# STM32G474R.net
KiCad netlist of a schematic drawn in Altium Designer
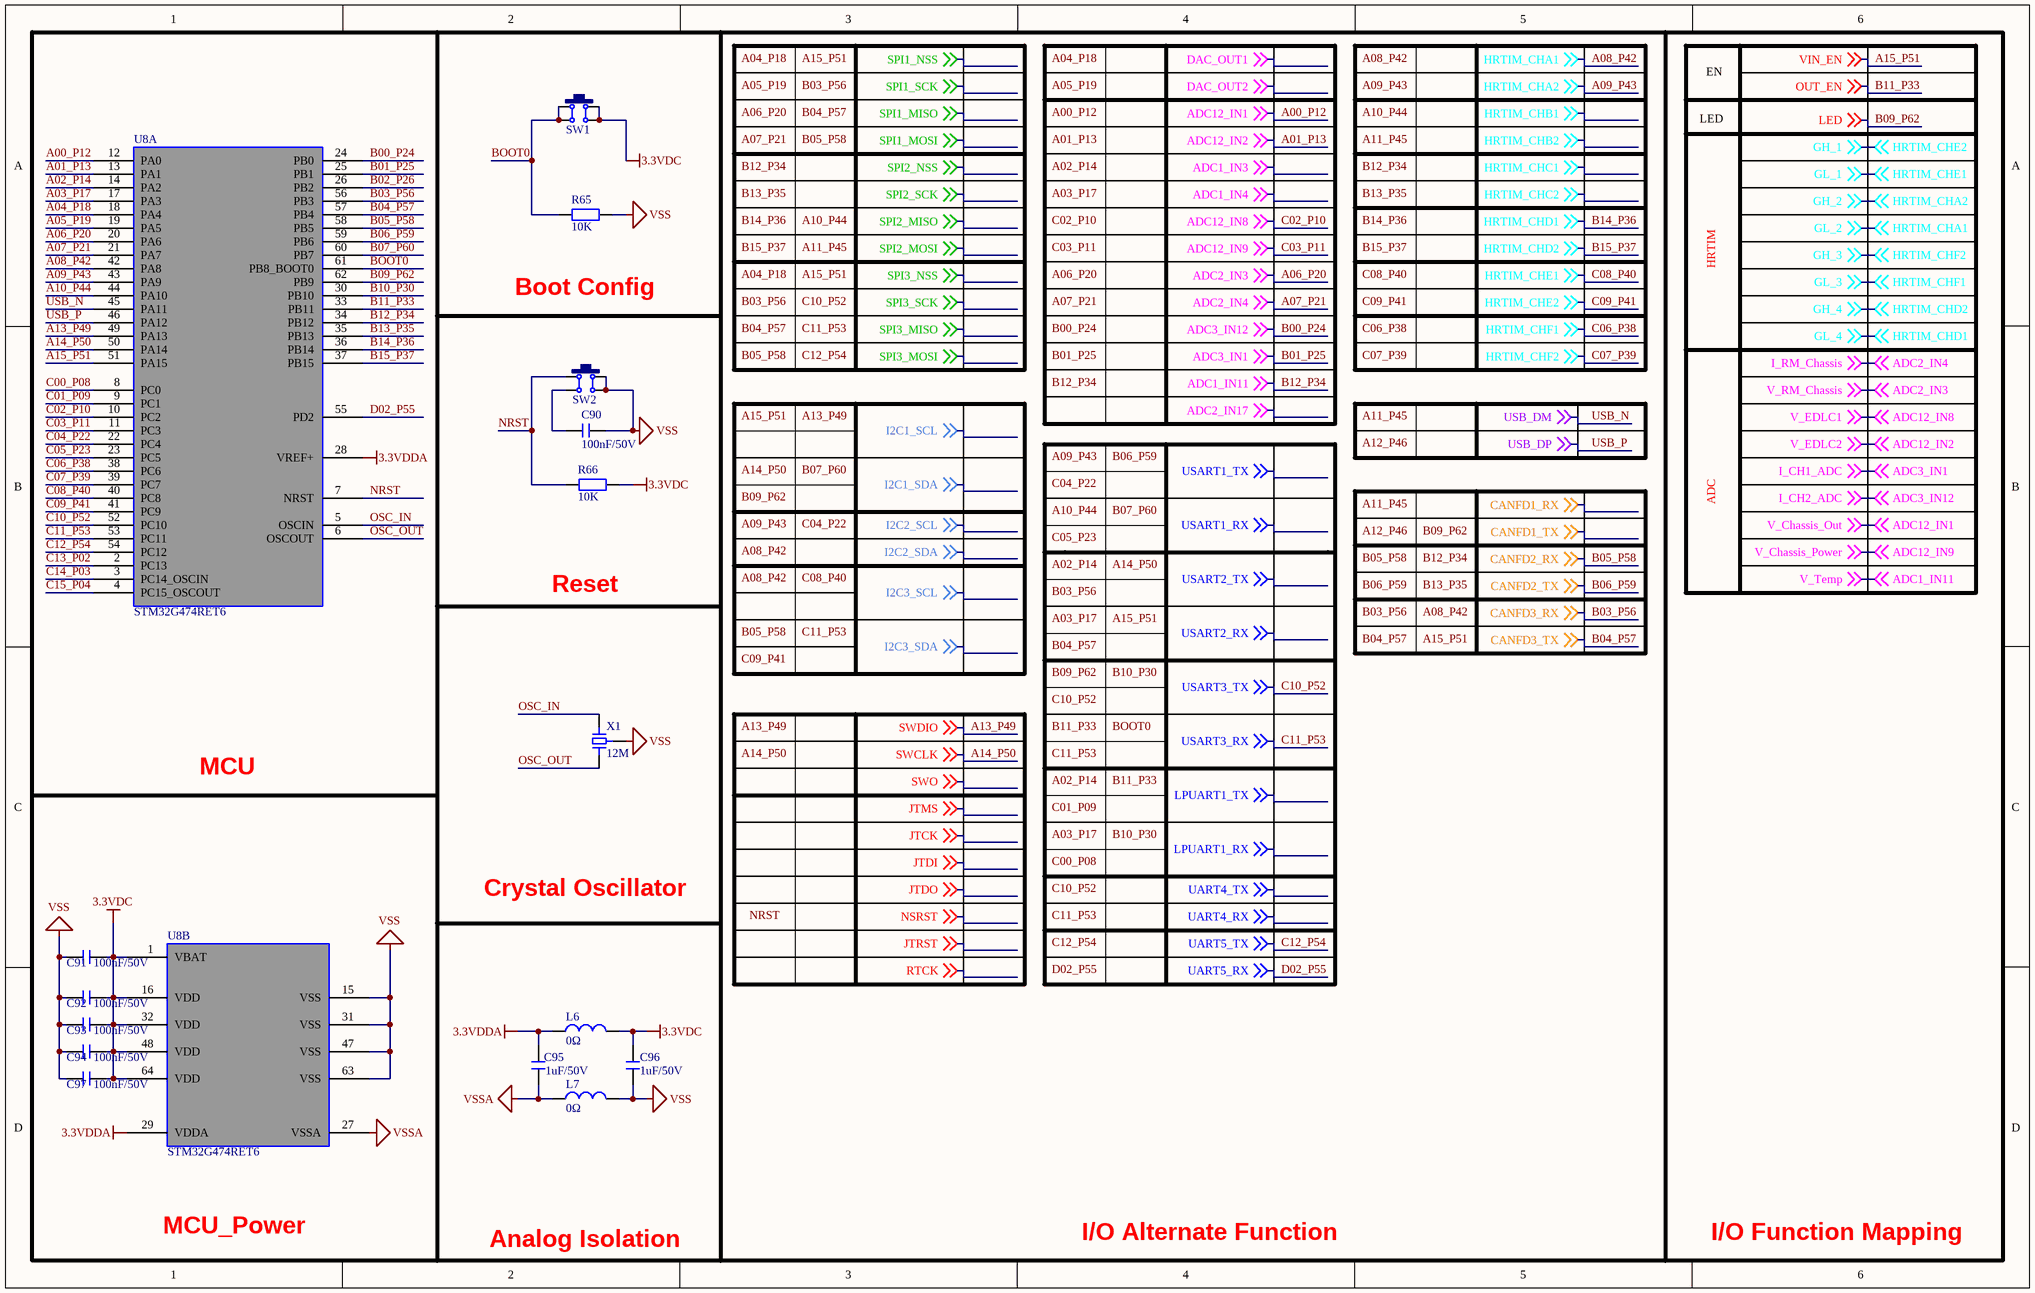
[diagram p0: STM32G474R.SchDoc]

(export (version "E")
  (design (tool "Eeschema 10.0.6"))
  (components
    (comp (ref "C90")
      (value "100nF/50V")
      (footprint "C 0603_L")
      (description "无极性贴片电容")
      (fields (field (name "版权归属") "源创客"))
      (libsource (lib "3.2-电容") (part "C"))
    )
    (comp (ref "C91")
      (value "100nF/50V")
      (footprint "C 0603_L")
      (description "无极性贴片电容")
      (fields (field (name "版权归属") "源创客"))
      (libsource (lib "3.2-电容") (part "C"))
    )
    (comp (ref "C92")
      (value "100nF/50V")
      (footprint "C 0603_L")
      (description "无极性贴片电容")
      (fields (field (name "版权归属") "源创客"))
      (libsource (lib "3.2-电容") (part "C"))
    )
    (comp (ref "C93")
      (value "100nF/50V")
      (footprint "C 0603_L")
      (description "无极性贴片电容")
      (fields (field (name "版权归属") "源创客"))
      (libsource (lib "3.2-电容") (part "C"))
    )
    (comp (ref "C94")
      (value "100nF/50V")
      (footprint "C 0603_L")
      (description "无极性贴片电容")
      (fields (field (name "版权归属") "源创客"))
      (libsource (lib "3.2-电容") (part "C"))
    )
    (comp (ref "C95")
      (value "1uF/50V")
      (footprint "C 0603_L")
      (description "无极性贴片电容")
      (fields (field (name "版权归属") "源创客"))
      (libsource (lib "3.2-电容") (part "C"))
    )
    (comp (ref "C96")
      (value "1uF/50V")
      (footprint "C 0603_L")
      (description "无极性贴片电容")
      (fields (field (name "版权归属") "源创客"))
      (libsource (lib "3.2-电容") (part "C"))
    )
    (comp (ref "C97")
      (value "100nF/50V")
      (footprint "C 0603_L")
      (description "无极性贴片电容")
      (fields (field (name "版权归属") "源创客"))
      (libsource (lib "3.2-电容") (part "C"))
    )
    (comp (ref "L6")
      (value "0Ω")
      (footprint "L 0603")
      (description "小功率贴片电感")
      (fields (field (name "版权归属") "源创客"))
      (libsource (lib "3.3-电感") (part "L"))
    )
    (comp (ref "L7")
      (value "0Ω")
      (footprint "L 0603")
      (description "小功率贴片电感")
      (fields (field (name "版权归属") "源创客"))
      (libsource (lib "3.3-电感") (part "L"))
    )
    (comp (ref "R65")
      (value "10K")
      (footprint "R 0603_L")
      (description "贴片电阻")
      (fields (field (name "版权归属") "源创客"))
      (libsource (lib "3.1-电阻") (part "R"))
    )
    (comp (ref "R66")
      (value "10K")
      (footprint "R 0603_L")
      (description "贴片电阻")
      (fields (field (name "版权归属") "源创客"))
      (libsource (lib "3.1-电阻") (part "R"))
    )
    (comp (ref "SW1")
      (value "3.2x4.2x2.5")
      (footprint "TSW SMD-3.2*4.2*2.5")
      (description "3.2x4.2轻触开关")
      (fields (field (name "版权归属") "源创客"))
      (libsource (lib "6.1-按键") (part "TSW SMD-3x4_D"))
    )
    (comp (ref "SW2")
      (value "3.2x4.2x2.5")
      (footprint "TSW SMD-3.2*4.2*2.5")
      (description "3.2x4.2轻触开关")
      (fields (field (name "版权归属") "源创客"))
      (libsource (lib "6.1-按键") (part "TSW SMD-3x4_D"))
    )
    (comp (ref "U8")
      (value "STM32G474RET6")
      (footprint "LQFP64-10*10")
      (libsource (lib "2.5-STM32G4单片机") (part "STM32G474RET6"))
    )
    (comp (ref "X1")
      (value "12M")
      (footprint "OSC 3213-3P")
      (description "3脚内置电容无源晶振")
      (libsource (lib "8.1-晶振") (part "XTAL-3P"))
    )
  )
  (nets
    (net (code "2") (name "/A02_P14") (class "Default")
      (node (ref "U8") (pin "14") (pinfunction "PA2_14") (pintype "passive"))
    )
    (net (code "3") (name "/A03_P17") (class "Default")
      (node (ref "U8") (pin "17") (pinfunction "PA3_17") (pintype "passive"))
    )
    (net (code "4") (name "/A04_P18") (class "Default")
      (node (ref "U8") (pin "18") (pinfunction "PA4_18") (pintype "passive"))
    )
    (net (code "5") (name "/A05_P19") (class "Default")
      (node (ref "U8") (pin "19") (pinfunction "PA5_19") (pintype "passive"))
    )
    (net (code "6") (name "/A10_P44") (class "Default")
      (node (ref "U8") (pin "44") (pinfunction "PA10_44") (pintype "passive"))
    )
    (net (code "9") (name "/B02_P26") (class "Default")
      (node (ref "U8") (pin "26") (pinfunction "PB2_26") (pintype "passive"))
    )
    (net (code "10") (name "/B07_P60") (class "Default")
      (node (ref "U8") (pin "60") (pinfunction "PB7_60") (pintype "passive"))
    )
    (net (code "11") (name "/B10_P30") (class "Default")
      (node (ref "U8") (pin "30") (pinfunction "PB10_30") (pintype "passive"))
    )
    (net (code "12") (name "/B13_P35") (class "Default")
      (node (ref "U8") (pin "35") (pinfunction "PB13_35") (pintype "passive"))
    )
    (net (code "13") (name "/BOOT0") (class "Default")
      (node (ref "R65") (pin "2") (pinfunction "2_2") (pintype "passive"))
      (node (ref "SW1") (pin "2") (pinfunction "2_2") (pintype "passive"))
      (node (ref "SW1") (pin "3") (pinfunction "3_3") (pintype "passive"))
      (node (ref "U8") (pin "61") (pinfunction "PB8_BOOT0_61") (pintype "passive"))
    )
    (net (code "14") (name "/C00_P08") (class "Default")
      (node (ref "U8") (pin "8") (pinfunction "PC0_8") (pintype "passive"))
    )
    (net (code "15") (name "/C01_P09") (class "Default")
      (node (ref "U8") (pin "9") (pinfunction "PC1_9") (pintype "passive"))
    )
    (net (code "16") (name "/C04_P22") (class "Default")
      (node (ref "U8") (pin "22") (pinfunction "PC4_22") (pintype "passive"))
    )
    (net (code "17") (name "/C05_P23") (class "Default")
      (node (ref "U8") (pin "23") (pinfunction "PC5_23") (pintype "passive"))
    )
    (net (code "18") (name "/C13_P02") (class "Default")
      (node (ref "U8") (pin "2") (pinfunction "PC13_2") (pintype "passive"))
    )
    (net (code "19") (name "/C14_P03") (class "Default")
      (node (ref "U8") (pin "3") (pinfunction "PC14_OSCIN_3") (pintype "passive"))
    )
    (net (code "20") (name "/C15_P04") (class "Default")
      (node (ref "U8") (pin "4") (pinfunction "PC15_OSCOUT_4") (pintype "passive"))
    )
    (net (code "21") (name "/NRST") (class "Default")
      (node (ref "R66") (pin "2") (pinfunction "2_2") (pintype "passive"))
      (node (ref "SW2") (pin "2") (pinfunction "2_2") (pintype "passive"))
      (node (ref "U8") (pin "7") (pinfunction "NRST_7") (pintype "passive"))
    )
    (net (code "22") (name "/OSC_IN") (class "Default")
      (node (ref "U8") (pin "5") (pinfunction "OSCIN_5") (pintype "passive"))
      (node (ref "X1") (pin "2") (pinfunction "2_2") (pintype "passive"))
    )
    (net (code "23") (name "/OSC_OUT") (class "Default")
      (node (ref "U8") (pin "6") (pinfunction "OSCOUT_6") (pintype "passive"))
      (node (ref "X1") (pin "1") (pinfunction "1_1") (pintype "passive"))
    )
    (net (code "24") (name "3.3VDC") (class "Default")
      (node (ref "C91") (pin "2") (pinfunction "2_2") (pintype "passive"))
      (node (ref "C92") (pin "2") (pinfunction "2_2") (pintype "passive"))
      (node (ref "C93") (pin "2") (pinfunction "2_2") (pintype "passive"))
      (node (ref "C94") (pin "2") (pinfunction "2_2") (pintype "passive"))
      (node (ref "C96") (pin "2") (pinfunction "2_2") (pintype "passive"))
      (node (ref "C97") (pin "2") (pinfunction "2_2") (pintype "passive"))
      (node (ref "L6") (pin "2") (pinfunction "2_2") (pintype "passive"))
      (node (ref "R66") (pin "1") (pinfunction "1_1") (pintype "passive"))
      (node (ref "SW1") (pin "1") (pinfunction "1_1") (pintype "passive"))
      (node (ref "SW1") (pin "4") (pinfunction "4_4") (pintype "passive"))
      (node (ref "U8") (pin "1") (pinfunction "VBAT_1") (pintype "passive"))
      (node (ref "U8") (pin "16") (pinfunction "VDD_16") (pintype "passive"))
      (node (ref "U8") (pin "32") (pinfunction "VDD_32") (pintype "passive"))
      (node (ref "U8") (pin "48") (pinfunction "VDD_48") (pintype "passive"))
      (node (ref "U8") (pin "64") (pinfunction "VDD_64") (pintype "passive"))
    )
    (net (code "25") (name "3.3VDDA") (class "Default")
      (node (ref "C95") (pin "2") (pinfunction "2_2") (pintype "passive"))
      (node (ref "L6") (pin "1") (pinfunction "1_1") (pintype "passive"))
      (node (ref "U8") (pin "28") (pinfunction "VREF+_28") (pintype "passive"))
      (node (ref "U8") (pin "29") (pinfunction "VDDA_29") (pintype "passive"))
    )
    (net (code "28") (name "ADC1_IN11") (class "Default")
      (node (ref "U8") (pin "34") (pinfunction "PB12_34") (pintype "passive"))
    )
    (net (code "29") (name "ADC2_IN3") (class "Default")
      (node (ref "U8") (pin "20") (pinfunction "PA6_20") (pintype "passive"))
    )
    (net (code "30") (name "ADC2_IN4") (class "Default")
      (node (ref "U8") (pin "21") (pinfunction "PA7_21") (pintype "passive"))
    )
    (net (code "32") (name "ADC3_IN1") (class "Default")
      (node (ref "U8") (pin "25") (pinfunction "PB1_25") (pintype "passive"))
    )
    (net (code "33") (name "ADC3_IN12") (class "Default")
      (node (ref "U8") (pin "24") (pinfunction "PB0_24") (pintype "passive"))
    )
    (net (code "34") (name "ADC12_IN1") (class "Default")
      (node (ref "U8") (pin "12") (pinfunction "PA0_12") (pintype "passive"))
    )
    (net (code "35") (name "ADC12_IN2") (class "Default")
      (node (ref "U8") (pin "13") (pinfunction "PA1_13") (pintype "passive"))
    )
    (net (code "36") (name "ADC12_IN8") (class "Default")
      (node (ref "U8") (pin "10") (pinfunction "PC2_10") (pintype "passive"))
    )
    (net (code "37") (name "ADC12_IN9") (class "Default")
      (node (ref "U8") (pin "11") (pinfunction "PC3_11") (pintype "passive"))
    )
    (net (code "40") (name "CANFD2_RX") (class "Default")
      (node (ref "U8") (pin "58") (pinfunction "PB5_58") (pintype "passive"))
    )
    (net (code "41") (name "CANFD2_TX") (class "Default")
      (node (ref "U8") (pin "59") (pinfunction "PB6_59") (pintype "passive"))
    )
    (net (code "42") (name "CANFD3_RX") (class "Default")
      (node (ref "U8") (pin "56") (pinfunction "PB3_56") (pintype "passive"))
    )
    (net (code "43") (name "CANFD3_TX") (class "Default")
      (node (ref "U8") (pin "57") (pinfunction "PB4_57") (pintype "passive"))
    )
    (net (code "46") (name "GH_1") (class "Default")
      (node (ref "U8") (pin "41") (pinfunction "PC9_41") (pintype "passive"))
    )
    (net (code "47") (name "GH_2") (class "Default")
      (node (ref "U8") (pin "43") (pinfunction "PA9_43") (pintype "passive"))
    )
    (net (code "48") (name "GH_3") (class "Default")
      (node (ref "U8") (pin "39") (pinfunction "PC7_39") (pintype "passive"))
    )
    (net (code "49") (name "GH_4") (class "Default")
      (node (ref "U8") (pin "37") (pinfunction "PB15_37") (pintype "passive"))
    )
    (net (code "50") (name "GL_1") (class "Default")
      (node (ref "U8") (pin "40") (pinfunction "PC8_40") (pintype "passive"))
    )
    (net (code "51") (name "GL_2") (class "Default")
      (node (ref "U8") (pin "42") (pinfunction "PA8_42") (pintype "passive"))
    )
    (net (code "52") (name "GL_3") (class "Default")
      (node (ref "U8") (pin "38") (pinfunction "PC6_38") (pintype "passive"))
    )
    (net (code "53") (name "GL_4") (class "Default")
      (node (ref "U8") (pin "36") (pinfunction "PB14_36") (pintype "passive"))
    )
    (net (code "69") (name "LED") (class "Default")
      (node (ref "U8") (pin "62") (pinfunction "PB9_62") (pintype "passive"))
    )
    (net (code "73") (name "Net-(C90-Pad1)") (class "Default")
      (node (ref "C90") (pin "1") (pinfunction "1_1") (pintype "passive"))
      (node (ref "SW2") (pin "3") (pinfunction "3_3") (pintype "passive"))
    )
    (net (code "74") (name "OUT_EN") (class "Default")
      (node (ref "U8") (pin "33") (pinfunction "PB11_33") (pintype "passive"))
    )
    (net (code "88") (name "SWCLK") (class "Default")
      (node (ref "U8") (pin "50") (pinfunction "PA14_50") (pintype "passive"))
    )
    (net (code "89") (name "SWDIO") (class "Default")
      (node (ref "U8") (pin "49") (pinfunction "PA13_49") (pintype "passive"))
    )
    (net (code "93") (name "UART5_RX") (class "Default")
      (node (ref "U8") (pin "55") (pinfunction "PD2_55") (pintype "passive"))
    )
    (net (code "94") (name "UART5_TX") (class "Default")
      (node (ref "U8") (pin "54") (pinfunction "PC12_54") (pintype "passive"))
    )
    (net (code "99") (name "USART3_RX") (class "Default")
      (node (ref "U8") (pin "53") (pinfunction "PC11_53") (pintype "passive"))
    )
    (net (code "100") (name "USART3_TX") (class "Default")
      (node (ref "U8") (pin "52") (pinfunction "PC10_52") (pintype "passive"))
    )
    (net (code "101") (name "USB_DM") (class "Default")
      (node (ref "U8") (pin "45") (pinfunction "PA11_45") (pintype "passive"))
    )
    (net (code "102") (name "USB_DP") (class "Default")
      (node (ref "U8") (pin "46") (pinfunction "PA12_46") (pintype "passive"))
    )
    (net (code "103") (name "VIN_EN") (class "Default")
      (node (ref "U8") (pin "51") (pinfunction "PA15_51") (pintype "passive"))
    )
    (net (code "104") (name "VSS") (class "Default")
      (node (ref "C90") (pin "2") (pinfunction "2_2") (pintype "passive"))
      (node (ref "C91") (pin "1") (pinfunction "1_1") (pintype "passive"))
      (node (ref "C92") (pin "1") (pinfunction "1_1") (pintype "passive"))
      (node (ref "C93") (pin "1") (pinfunction "1_1") (pintype "passive"))
      (node (ref "C94") (pin "1") (pinfunction "1_1") (pintype "passive"))
      (node (ref "C96") (pin "1") (pinfunction "1_1") (pintype "passive"))
      (node (ref "C97") (pin "1") (pinfunction "1_1") (pintype "passive"))
      (node (ref "L7") (pin "2") (pinfunction "2_2") (pintype "passive"))
      (node (ref "R65") (pin "1") (pinfunction "1_1") (pintype "passive"))
      (node (ref "SW2") (pin "1") (pinfunction "1_1") (pintype "passive"))
      (node (ref "SW2") (pin "4") (pinfunction "4_4") (pintype "passive"))
      (node (ref "U8") (pin "15") (pinfunction "VSS_15") (pintype "passive"))
      (node (ref "U8") (pin "31") (pinfunction "VSS_31") (pintype "passive"))
      (node (ref "U8") (pin "47") (pinfunction "VSS_47") (pintype "passive"))
      (node (ref "U8") (pin "63") (pinfunction "VSS_63") (pintype "passive"))
      (node (ref "X1") (pin "3") (pinfunction "3_3") (pintype "passive"))
    )
    (net (code "105") (name "VSSA") (class "Default")
      (node (ref "C95") (pin "1") (pinfunction "1_1") (pintype "passive"))
      (node (ref "L7") (pin "1") (pinfunction "1_1") (pintype "passive"))
      (node (ref "U8") (pin "27") (pinfunction "VSSA_27") (pintype "passive"))
    )
  )
)
